# Solar_Panel_Connectors.net
KiCad netlist of a schematic drawn in Altium Designer
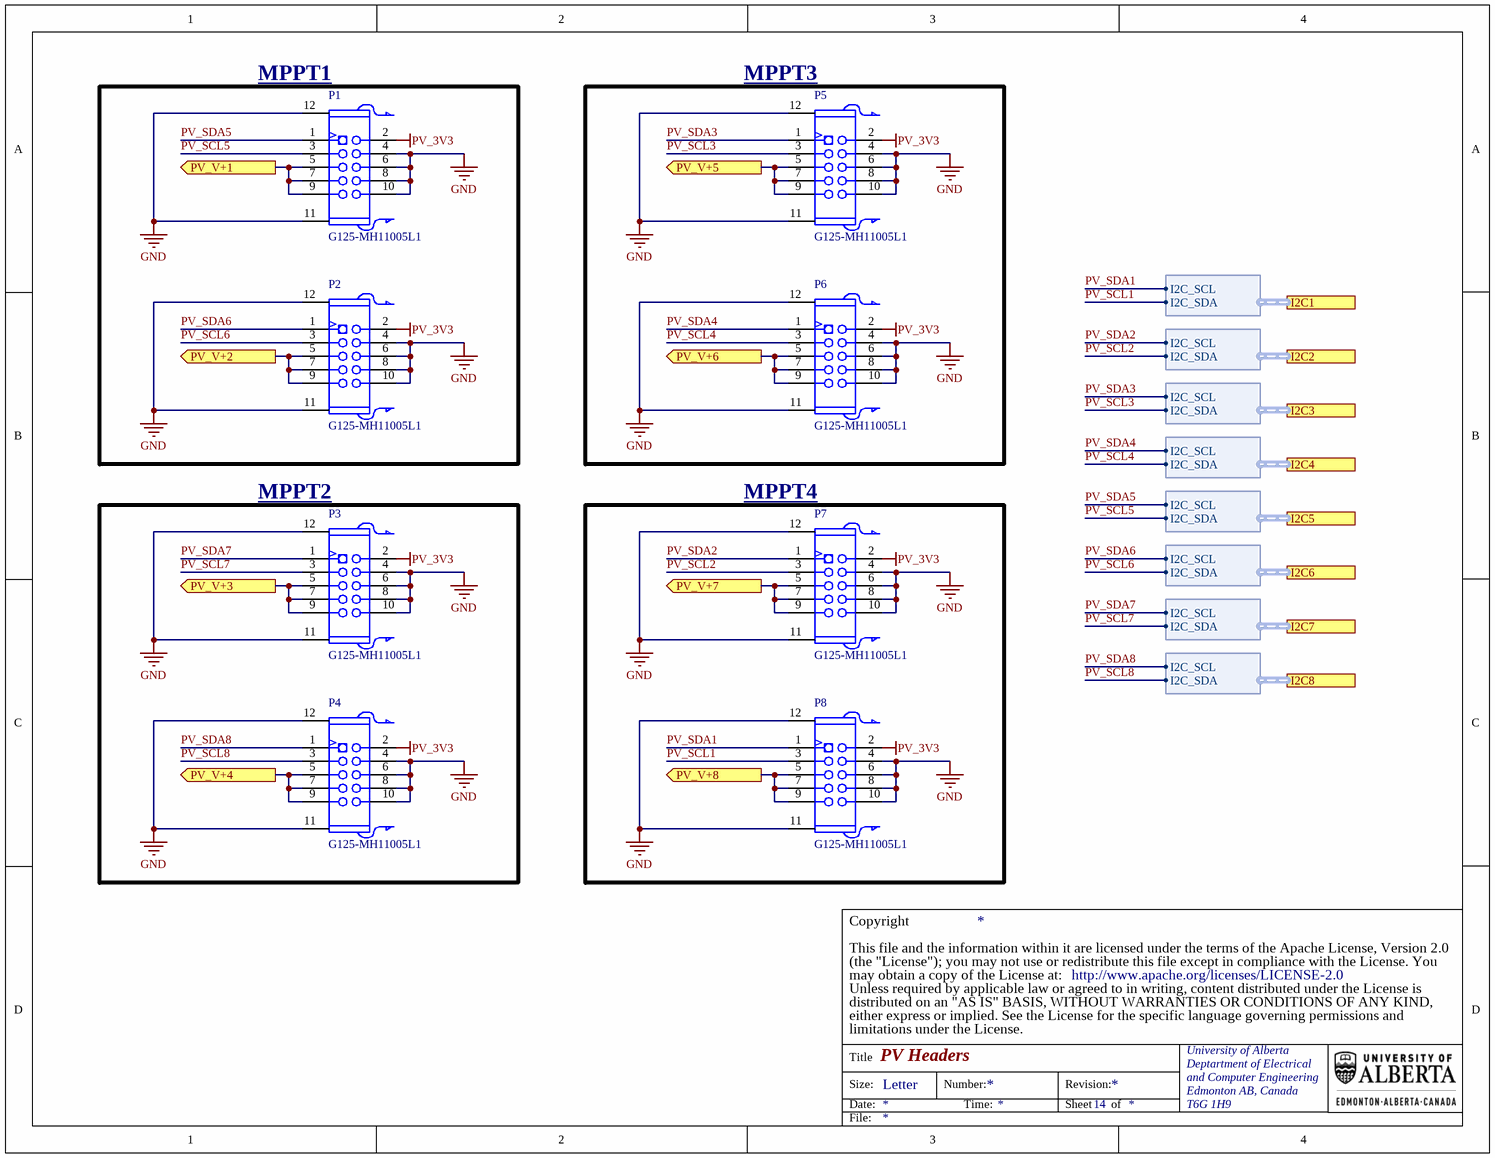
[diagram p0: Solar Panel Connectors.SchDoc]

(export (version "E")
  (design (tool "Eeschema 10.0.6"))
  (components
    (comp (ref "P1")
      (value "G125-MH11005L1")
      (footprint "HWN-G125-MH11005L1")
      (description "CONN HEADER R/A 10POS 1.25MM")
      (fields
        (field (name "PART NUMBER") "PP-HWN-00015")
        (field (name "MANUFACTURER PART NUMBER") "G125-MH11005L1P")
        (field (name "PUBLISHER") "AlbertaSat")
      )
      (libsource (lib "Database") (part "G125-MH11005L1P"))
    )
    (comp (ref "P2")
      (value "G125-MH11005L1")
      (footprint "HWN-G125-MH11005L1")
      (description "CONN HEADER R/A 10POS 1.25MM")
      (fields
        (field (name "PART NUMBER") "PP-HWN-00015")
        (field (name "MANUFACTURER PART NUMBER") "G125-MH11005L1P")
        (field (name "PUBLISHER") "AlbertaSat")
      )
      (libsource (lib "Database") (part "G125-MH11005L1P"))
    )
    (comp (ref "P3")
      (value "G125-MH11005L1")
      (footprint "HWN-G125-MH11005L1")
      (description "CONN HEADER R/A 10POS 1.25MM")
      (fields
        (field (name "PART NUMBER") "PP-HWN-00015")
        (field (name "MANUFACTURER PART NUMBER") "G125-MH11005L1P")
        (field (name "PUBLISHER") "AlbertaSat")
      )
      (libsource (lib "Database") (part "G125-MH11005L1P"))
    )
    (comp (ref "P4")
      (value "G125-MH11005L1")
      (footprint "HWN-G125-MH11005L1")
      (description "CONN HEADER R/A 10POS 1.25MM")
      (fields
        (field (name "PART NUMBER") "PP-HWN-00015")
        (field (name "MANUFACTURER PART NUMBER") "G125-MH11005L1P")
        (field (name "PUBLISHER") "AlbertaSat")
      )
      (libsource (lib "Database") (part "G125-MH11005L1P"))
    )
    (comp (ref "P5")
      (value "G125-MH11005L1")
      (footprint "HWN-G125-MH11005L1")
      (description "CONN HEADER R/A 10POS 1.25MM")
      (fields
        (field (name "PART NUMBER") "PP-HWN-00015")
        (field (name "MANUFACTURER PART NUMBER") "G125-MH11005L1P")
        (field (name "PUBLISHER") "AlbertaSat")
      )
      (libsource (lib "Database") (part "G125-MH11005L1P"))
    )
    (comp (ref "P6")
      (value "G125-MH11005L1")
      (footprint "HWN-G125-MH11005L1")
      (description "CONN HEADER R/A 10POS 1.25MM")
      (fields
        (field (name "PART NUMBER") "PP-HWN-00015")
        (field (name "MANUFACTURER PART NUMBER") "G125-MH11005L1P")
        (field (name "PUBLISHER") "AlbertaSat")
      )
      (libsource (lib "Database") (part "G125-MH11005L1P"))
    )
    (comp (ref "P7")
      (value "G125-MH11005L1")
      (footprint "HWN-G125-MH11005L1")
      (description "CONN HEADER R/A 10POS 1.25MM")
      (fields
        (field (name "PART NUMBER") "PP-HWN-00015")
        (field (name "MANUFACTURER PART NUMBER") "G125-MH11005L1P")
        (field (name "PUBLISHER") "AlbertaSat")
      )
      (libsource (lib "Database") (part "G125-MH11005L1P"))
    )
    (comp (ref "P8")
      (value "G125-MH11005L1")
      (footprint "HWN-G125-MH11005L1")
      (description "CONN HEADER R/A 10POS 1.25MM")
      (fields
        (field (name "PART NUMBER") "PP-HWN-00015")
        (field (name "MANUFACTURER PART NUMBER") "G125-MH11005L1P")
        (field (name "PUBLISHER") "AlbertaSat")
      )
      (libsource (lib "Database") (part "G125-MH11005L1P"))
    )
  )
  (nets
    (net (code "9") (name "/PV_SCL1") (class "Default")
      (node (ref "P8") (pin "3") (pinfunction "3_3") (pintype "passive"))
    )
    (net (code "10") (name "/PV_SCL2") (class "Default")
      (node (ref "P7") (pin "3") (pinfunction "3_3") (pintype "passive"))
    )
    (net (code "11") (name "/PV_SCL3") (class "Default")
      (node (ref "P5") (pin "3") (pinfunction "3_3") (pintype "passive"))
    )
    (net (code "12") (name "/PV_SCL4") (class "Default")
      (node (ref "P6") (pin "3") (pinfunction "3_3") (pintype "passive"))
    )
    (net (code "13") (name "/PV_SCL5") (class "Default")
      (node (ref "P1") (pin "3") (pinfunction "3_3") (pintype "passive"))
    )
    (net (code "14") (name "/PV_SCL6") (class "Default")
      (node (ref "P2") (pin "3") (pinfunction "3_3") (pintype "passive"))
    )
    (net (code "15") (name "/PV_SCL7") (class "Default")
      (node (ref "P3") (pin "3") (pinfunction "3_3") (pintype "passive"))
    )
    (net (code "16") (name "/PV_SCL8") (class "Default")
      (node (ref "P4") (pin "3") (pinfunction "3_3") (pintype "passive"))
    )
    (net (code "17") (name "/PV_SDA1") (class "Default")
      (node (ref "P8") (pin "1") (pinfunction "1_1") (pintype "passive"))
    )
    (net (code "18") (name "/PV_SDA2") (class "Default")
      (node (ref "P7") (pin "1") (pinfunction "1_1") (pintype "passive"))
    )
    (net (code "19") (name "/PV_SDA3") (class "Default")
      (node (ref "P5") (pin "1") (pinfunction "1_1") (pintype "passive"))
    )
    (net (code "20") (name "/PV_SDA4") (class "Default")
      (node (ref "P6") (pin "1") (pinfunction "1_1") (pintype "passive"))
    )
    (net (code "21") (name "/PV_SDA5") (class "Default")
      (node (ref "P1") (pin "1") (pinfunction "1_1") (pintype "passive"))
    )
    (net (code "22") (name "/PV_SDA6") (class "Default")
      (node (ref "P2") (pin "1") (pinfunction "1_1") (pintype "passive"))
    )
    (net (code "23") (name "/PV_SDA7") (class "Default")
      (node (ref "P3") (pin "1") (pinfunction "1_1") (pintype "passive"))
    )
    (net (code "24") (name "/PV_SDA8") (class "Default")
      (node (ref "P4") (pin "1") (pinfunction "1_1") (pintype "passive"))
    )
    (net (code "25") (name "/PV_V+1") (class "Default")
      (node (ref "P1") (pin "5") (pinfunction "5_5") (pintype "passive"))
      (node (ref "P1") (pin "7") (pinfunction "7_7") (pintype "passive"))
      (node (ref "P1") (pin "9") (pinfunction "9_9") (pintype "passive"))
    )
    (net (code "26") (name "/PV_V+2") (class "Default")
      (node (ref "P2") (pin "5") (pinfunction "5_5") (pintype "passive"))
      (node (ref "P2") (pin "7") (pinfunction "7_7") (pintype "passive"))
      (node (ref "P2") (pin "9") (pinfunction "9_9") (pintype "passive"))
    )
    (net (code "27") (name "/PV_V+3") (class "Default")
      (node (ref "P3") (pin "5") (pinfunction "5_5") (pintype "passive"))
      (node (ref "P3") (pin "7") (pinfunction "7_7") (pintype "passive"))
      (node (ref "P3") (pin "9") (pinfunction "9_9") (pintype "passive"))
    )
    (net (code "28") (name "/PV_V+4") (class "Default")
      (node (ref "P4") (pin "5") (pinfunction "5_5") (pintype "passive"))
      (node (ref "P4") (pin "7") (pinfunction "7_7") (pintype "passive"))
      (node (ref "P4") (pin "9") (pinfunction "9_9") (pintype "passive"))
    )
    (net (code "29") (name "/PV_V+5") (class "Default")
      (node (ref "P5") (pin "5") (pinfunction "5_5") (pintype "passive"))
      (node (ref "P5") (pin "7") (pinfunction "7_7") (pintype "passive"))
      (node (ref "P5") (pin "9") (pinfunction "9_9") (pintype "passive"))
    )
    (net (code "30") (name "/PV_V+6") (class "Default")
      (node (ref "P6") (pin "5") (pinfunction "5_5") (pintype "passive"))
      (node (ref "P6") (pin "7") (pinfunction "7_7") (pintype "passive"))
      (node (ref "P6") (pin "9") (pinfunction "9_9") (pintype "passive"))
    )
    (net (code "31") (name "/PV_V+7") (class "Default")
      (node (ref "P7") (pin "5") (pinfunction "5_5") (pintype "passive"))
      (node (ref "P7") (pin "7") (pinfunction "7_7") (pintype "passive"))
      (node (ref "P7") (pin "9") (pinfunction "9_9") (pintype "passive"))
    )
    (net (code "32") (name "/PV_V+8") (class "Default")
      (node (ref "P8") (pin "5") (pinfunction "5_5") (pintype "passive"))
      (node (ref "P8") (pin "7") (pinfunction "7_7") (pintype "passive"))
      (node (ref "P8") (pin "9") (pinfunction "9_9") (pintype "passive"))
    )
    (net (code "41") (name "GND") (class "Default")
      (node (ref "P1") (pin "10") (pinfunction "10_10") (pintype "passive"))
      (node (ref "P1") (pin "11") (pinfunction "11_11") (pintype "passive"))
      (node (ref "P1") (pin "12") (pinfunction "12_12") (pintype "passive"))
      (node (ref "P1") (pin "4") (pinfunction "4_4") (pintype "passive"))
      (node (ref "P1") (pin "6") (pinfunction "6_6") (pintype "passive"))
      (node (ref "P1") (pin "8") (pinfunction "8_8") (pintype "passive"))
      (node (ref "P2") (pin "10") (pinfunction "10_10") (pintype "passive"))
      (node (ref "P2") (pin "11") (pinfunction "11_11") (pintype "passive"))
      (node (ref "P2") (pin "12") (pinfunction "12_12") (pintype "passive"))
      (node (ref "P2") (pin "4") (pinfunction "4_4") (pintype "passive"))
      (node (ref "P2") (pin "6") (pinfunction "6_6") (pintype "passive"))
      (node (ref "P2") (pin "8") (pinfunction "8_8") (pintype "passive"))
      (node (ref "P3") (pin "10") (pinfunction "10_10") (pintype "passive"))
      (node (ref "P3") (pin "11") (pinfunction "11_11") (pintype "passive"))
      (node (ref "P3") (pin "12") (pinfunction "12_12") (pintype "passive"))
      (node (ref "P3") (pin "4") (pinfunction "4_4") (pintype "passive"))
      (node (ref "P3") (pin "6") (pinfunction "6_6") (pintype "passive"))
      (node (ref "P3") (pin "8") (pinfunction "8_8") (pintype "passive"))
      (node (ref "P4") (pin "10") (pinfunction "10_10") (pintype "passive"))
      (node (ref "P4") (pin "11") (pinfunction "11_11") (pintype "passive"))
      (node (ref "P4") (pin "12") (pinfunction "12_12") (pintype "passive"))
      (node (ref "P4") (pin "4") (pinfunction "4_4") (pintype "passive"))
      (node (ref "P4") (pin "6") (pinfunction "6_6") (pintype "passive"))
      (node (ref "P4") (pin "8") (pinfunction "8_8") (pintype "passive"))
      (node (ref "P5") (pin "10") (pinfunction "10_10") (pintype "passive"))
      (node (ref "P5") (pin "11") (pinfunction "11_11") (pintype "passive"))
      (node (ref "P5") (pin "12") (pinfunction "12_12") (pintype "passive"))
      (node (ref "P5") (pin "4") (pinfunction "4_4") (pintype "passive"))
      (node (ref "P5") (pin "6") (pinfunction "6_6") (pintype "passive"))
      (node (ref "P5") (pin "8") (pinfunction "8_8") (pintype "passive"))
      (node (ref "P6") (pin "10") (pinfunction "10_10") (pintype "passive"))
      (node (ref "P6") (pin "11") (pinfunction "11_11") (pintype "passive"))
      (node (ref "P6") (pin "12") (pinfunction "12_12") (pintype "passive"))
      (node (ref "P6") (pin "4") (pinfunction "4_4") (pintype "passive"))
      (node (ref "P6") (pin "6") (pinfunction "6_6") (pintype "passive"))
      (node (ref "P6") (pin "8") (pinfunction "8_8") (pintype "passive"))
      (node (ref "P7") (pin "10") (pinfunction "10_10") (pintype "passive"))
      (node (ref "P7") (pin "11") (pinfunction "11_11") (pintype "passive"))
      (node (ref "P7") (pin "12") (pinfunction "12_12") (pintype "passive"))
      (node (ref "P7") (pin "4") (pinfunction "4_4") (pintype "passive"))
      (node (ref "P7") (pin "6") (pinfunction "6_6") (pintype "passive"))
      (node (ref "P7") (pin "8") (pinfunction "8_8") (pintype "passive"))
      (node (ref "P8") (pin "10") (pinfunction "10_10") (pintype "passive"))
      (node (ref "P8") (pin "11") (pinfunction "11_11") (pintype "passive"))
      (node (ref "P8") (pin "12") (pinfunction "12_12") (pintype "passive"))
      (node (ref "P8") (pin "4") (pinfunction "4_4") (pintype "passive"))
      (node (ref "P8") (pin "6") (pinfunction "6_6") (pintype "passive"))
      (node (ref "P8") (pin "8") (pinfunction "8_8") (pintype "passive"))
    )
    (net (code "42") (name "PV_3V3") (class "Default")
      (node (ref "P1") (pin "2") (pinfunction "2_2") (pintype "passive"))
      (node (ref "P2") (pin "2") (pinfunction "2_2") (pintype "passive"))
      (node (ref "P3") (pin "2") (pinfunction "2_2") (pintype "passive"))
      (node (ref "P4") (pin "2") (pinfunction "2_2") (pintype "passive"))
      (node (ref "P5") (pin "2") (pinfunction "2_2") (pintype "passive"))
      (node (ref "P6") (pin "2") (pinfunction "2_2") (pintype "passive"))
      (node (ref "P7") (pin "2") (pinfunction "2_2") (pintype "passive"))
      (node (ref "P8") (pin "2") (pinfunction "2_2") (pintype "passive"))
    )
  )
)
